# SD.net
KiCad netlist of a schematic drawn in EAGLE
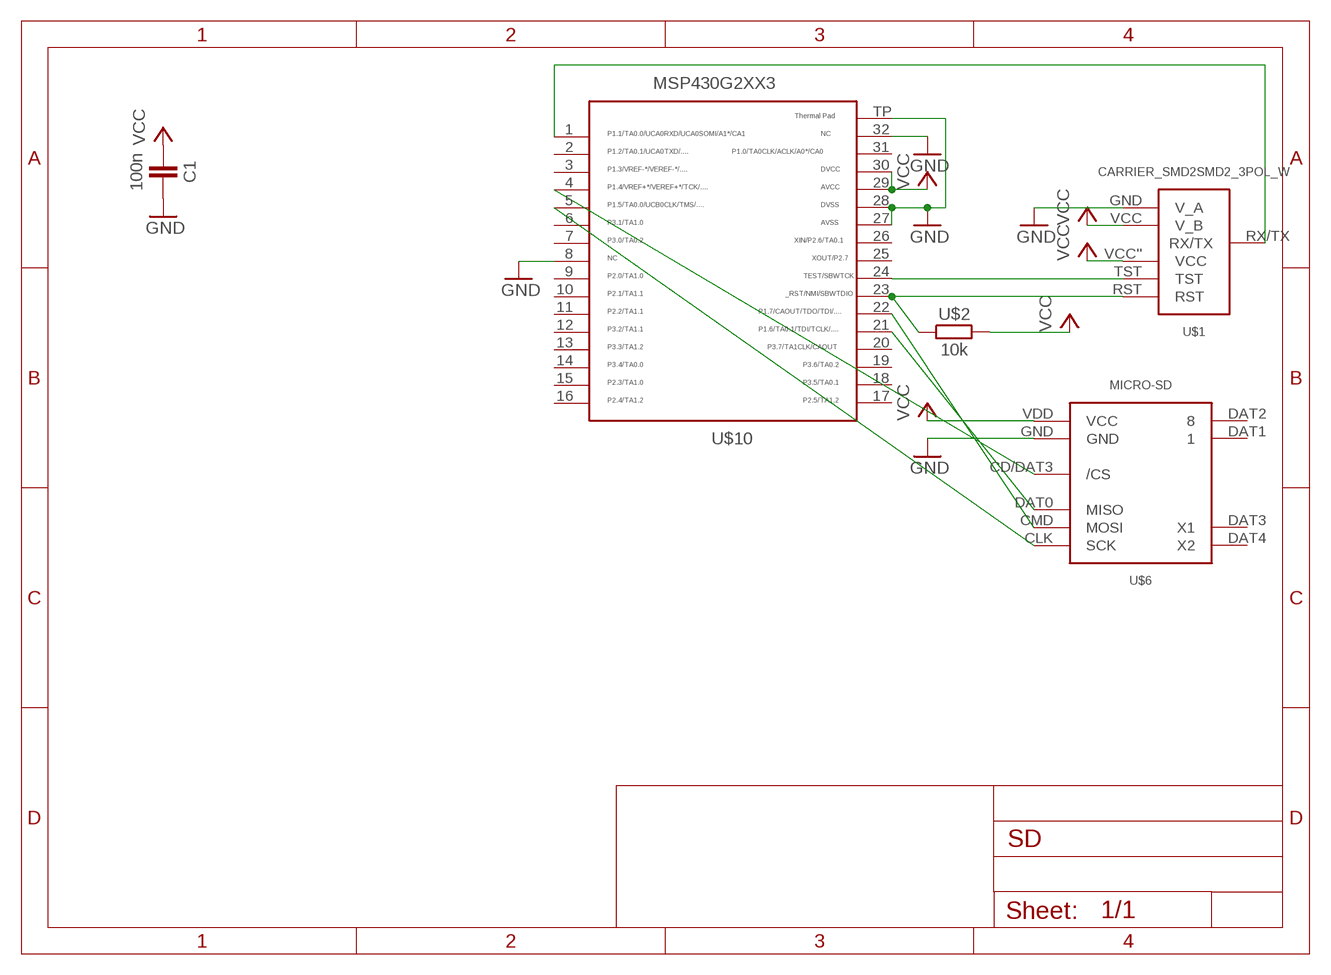
[diagram p0: schematic, sheet 1]

(export (version "E")
  (design (tool "Eeschema 10.0.6"))
  (components
    (comp (ref "C1")
      (value "100n")
      (footprint "eagle-import:603")
      (libsource (lib "eagle-import") (part "CAPACITOR"))
    )
    (comp (ref "U$1")
      (value "CARRIER_SMD2SMD2_3POL_W")
      (footprint "eagle-import:CARRIER_SMD2_WIDE_3POL")
      (libsource (lib "eagle-import") (part "CARRIER_SMD2SMD2_3POL_W"))
    )
    (comp (ref "U$2")
      (value "10k")
      (footprint "eagle-import:603")
      (libsource (lib "eagle-import") (part "RESISTOR0603"))
    )
    (comp (ref "U$6")
      (value "MICRO-SD")
      (footprint "eagle-import:SD-CARD-AMP")
      (libsource (lib "eagle-import") (part "MICRO-SD"))
    )
    (comp (ref "U$10")
      (value "MSP430G2553")
      (footprint "eagle-import:QFN32")
      (libsource (lib "eagle-import") (part "MSP430G2553"))
    )
  )
  (nets
    (net (code "1") (name "GND") (class "Default")
      (node (ref "C1") (pin "2") (pinfunction "2_2") (pintype "passive"))
      (node (ref "U$1") (pin "GND") (pinfunction "V_A_GND") (pintype "bidirectional"))
      (node (ref "U$10") (pin "27") (pinfunction "27_27") (pintype "bidirectional"))
      (node (ref "U$10") (pin "28") (pinfunction "28_28") (pintype "bidirectional"))
      (node (ref "U$10") (pin "32") (pinfunction "32_32") (pintype "bidirectional"))
      (node (ref "U$10") (pin "8") (pinfunction "8_8") (pintype "bidirectional"))
      (node (ref "U$10") (pin "TP") (pinfunction "TP_TP") (pintype "bidirectional"))
      (node (ref "U$6") (pin "GND") (pinfunction "GND_GND") (pintype "bidirectional"))
    )
    (net (code "2") (name "Net-(U$1-PadRST)") (class "Default")
      (node (ref "U$1") (pin "RST") (pinfunction "RST_RST") (pintype "bidirectional"))
      (node (ref "U$10") (pin "23") (pinfunction "23_23") (pintype "bidirectional"))
      (node (ref "U$2") (pin "1") (pinfunction "1_1") (pintype "passive"))
    )
    (net (code "3") (name "Net-(U$1-PadRX{slash}TX)") (class "Default")
      (node (ref "U$1") (pin "RX/TX") (pinfunction "RX/TX_RX/TX") (pintype "bidirectional"))
      (node (ref "U$10") (pin "1") (pinfunction "1_1") (pintype "bidirectional"))
    )
    (net (code "4") (name "Net-(U$1-PadTST)") (class "Default")
      (node (ref "U$1") (pin "TST") (pinfunction "TST_TST") (pintype "bidirectional"))
      (node (ref "U$10") (pin "24") (pinfunction "24_24") (pintype "bidirectional"))
    )
    (net (code "5") (name "Net-(U$6-MISO)") (class "Default")
      (node (ref "U$10") (pin "21") (pinfunction "21_21") (pintype "bidirectional"))
      (node (ref "U$6") (pin "DAT0") (pinfunction "MISO_DAT0") (pintype "bidirectional"))
    )
    (net (code "6") (name "Net-(U$6-MOSI)") (class "Default")
      (node (ref "U$10") (pin "22") (pinfunction "22_22") (pintype "bidirectional"))
      (node (ref "U$6") (pin "CMD") (pinfunction "MOSI_CMD") (pintype "bidirectional"))
    )
    (net (code "7") (name "Net-(U$6-SCK)") (class "Default")
      (node (ref "U$10") (pin "5") (pinfunction "5_5") (pintype "bidirectional"))
      (node (ref "U$6") (pin "CLK") (pinfunction "SCK_CLK") (pintype "bidirectional"))
    )
    (net (code "8") (name "Net-(U$6-{slash}CS)") (class "Default")
      (node (ref "U$10") (pin "4") (pinfunction "4_4") (pintype "bidirectional"))
      (node (ref "U$6") (pin "CD/DAT3") (pinfunction "/CS_CD/DAT3") (pintype "bidirectional"))
    )
    (net (code "9") (name "VCC") (class "Default")
      (node (ref "C1") (pin "1") (pinfunction "1_1") (pintype "passive"))
      (node (ref "U$1") (pin "VCC") (pinfunction "V_B_VCC") (pintype "bidirectional"))
      (node (ref "U$1") (pin "VCC''") (pinfunction "VCC_VCC''") (pintype "bidirectional"))
      (node (ref "U$10") (pin "29") (pinfunction "29_29") (pintype "bidirectional"))
      (node (ref "U$10") (pin "30") (pinfunction "30_30") (pintype "bidirectional"))
      (node (ref "U$2") (pin "2") (pinfunction "2_2") (pintype "passive"))
      (node (ref "U$6") (pin "VDD") (pinfunction "VCC_VDD") (pintype "bidirectional"))
    )
    (net (code "10") (name "unconnected-(U$6-1-PadDAT1)") (class "Default")
      (node (ref "U$6") (pin "DAT1") (pinfunction "1_DAT1") (pintype "bidirectional"))
    )
    (net (code "11") (name "unconnected-(U$6-8-PadDAT2)") (class "Default")
      (node (ref "U$6") (pin "DAT2") (pinfunction "8_DAT2") (pintype "bidirectional"))
    )
    (net (code "12") (name "unconnected-(U$6-X1-PadDAT3)") (class "Default")
      (node (ref "U$6") (pin "DAT3") (pinfunction "X1_DAT3") (pintype "bidirectional"))
    )
    (net (code "13") (name "unconnected-(U$6-X2-PadDAT4)") (class "Default")
      (node (ref "U$6") (pin "DAT4") (pinfunction "X2_DAT4") (pintype "bidirectional"))
    )
    (net (code "14") (name "unconnected-(U$10-Pad2)") (class "Default")
      (node (ref "U$10") (pin "2") (pinfunction "2_2") (pintype "bidirectional"))
    )
    (net (code "15") (name "unconnected-(U$10-Pad3)") (class "Default")
      (node (ref "U$10") (pin "3") (pinfunction "3_3") (pintype "bidirectional"))
    )
    (net (code "16") (name "unconnected-(U$10-Pad6)") (class "Default")
      (node (ref "U$10") (pin "6") (pinfunction "6_6") (pintype "bidirectional"))
    )
    (net (code "17") (name "unconnected-(U$10-Pad7)") (class "Default")
      (node (ref "U$10") (pin "7") (pinfunction "7_7") (pintype "bidirectional"))
    )
    (net (code "18") (name "unconnected-(U$10-Pad9)") (class "Default")
      (node (ref "U$10") (pin "9") (pinfunction "9_9") (pintype "bidirectional"))
    )
    (net (code "19") (name "unconnected-(U$10-Pad10)") (class "Default")
      (node (ref "U$10") (pin "10") (pinfunction "10_10") (pintype "bidirectional"))
    )
    (net (code "20") (name "unconnected-(U$10-Pad11)") (class "Default")
      (node (ref "U$10") (pin "11") (pinfunction "11_11") (pintype "bidirectional"))
    )
    (net (code "21") (name "unconnected-(U$10-Pad12)") (class "Default")
      (node (ref "U$10") (pin "12") (pinfunction "12_12") (pintype "bidirectional"))
    )
    (net (code "22") (name "unconnected-(U$10-Pad13)") (class "Default")
      (node (ref "U$10") (pin "13") (pinfunction "13_13") (pintype "bidirectional"))
    )
    (net (code "23") (name "unconnected-(U$10-Pad14)") (class "Default")
      (node (ref "U$10") (pin "14") (pinfunction "14_14") (pintype "bidirectional"))
    )
    (net (code "24") (name "unconnected-(U$10-Pad15)") (class "Default")
      (node (ref "U$10") (pin "15") (pinfunction "15_15") (pintype "bidirectional"))
    )
    (net (code "25") (name "unconnected-(U$10-Pad16)") (class "Default")
      (node (ref "U$10") (pin "16") (pinfunction "16_16") (pintype "bidirectional"))
    )
    (net (code "26") (name "unconnected-(U$10-Pad17)") (class "Default")
      (node (ref "U$10") (pin "17") (pinfunction "17_17") (pintype "bidirectional"))
    )
    (net (code "27") (name "unconnected-(U$10-Pad18)") (class "Default")
      (node (ref "U$10") (pin "18") (pinfunction "18_18") (pintype "bidirectional"))
    )
    (net (code "28") (name "unconnected-(U$10-Pad19)") (class "Default")
      (node (ref "U$10") (pin "19") (pinfunction "19_19") (pintype "bidirectional"))
    )
    (net (code "29") (name "unconnected-(U$10-Pad20)") (class "Default")
      (node (ref "U$10") (pin "20") (pinfunction "20_20") (pintype "bidirectional"))
    )
    (net (code "30") (name "unconnected-(U$10-Pad25)") (class "Default")
      (node (ref "U$10") (pin "25") (pinfunction "25_25") (pintype "bidirectional"))
    )
    (net (code "31") (name "unconnected-(U$10-Pad26)") (class "Default")
      (node (ref "U$10") (pin "26") (pinfunction "26_26") (pintype "bidirectional"))
    )
    (net (code "32") (name "unconnected-(U$10-Pad31)") (class "Default")
      (node (ref "U$10") (pin "31") (pinfunction "31_31") (pintype "bidirectional"))
    )
  )
)
